# main.net
KiCad netlist of a schematic drawn in Altium Designer
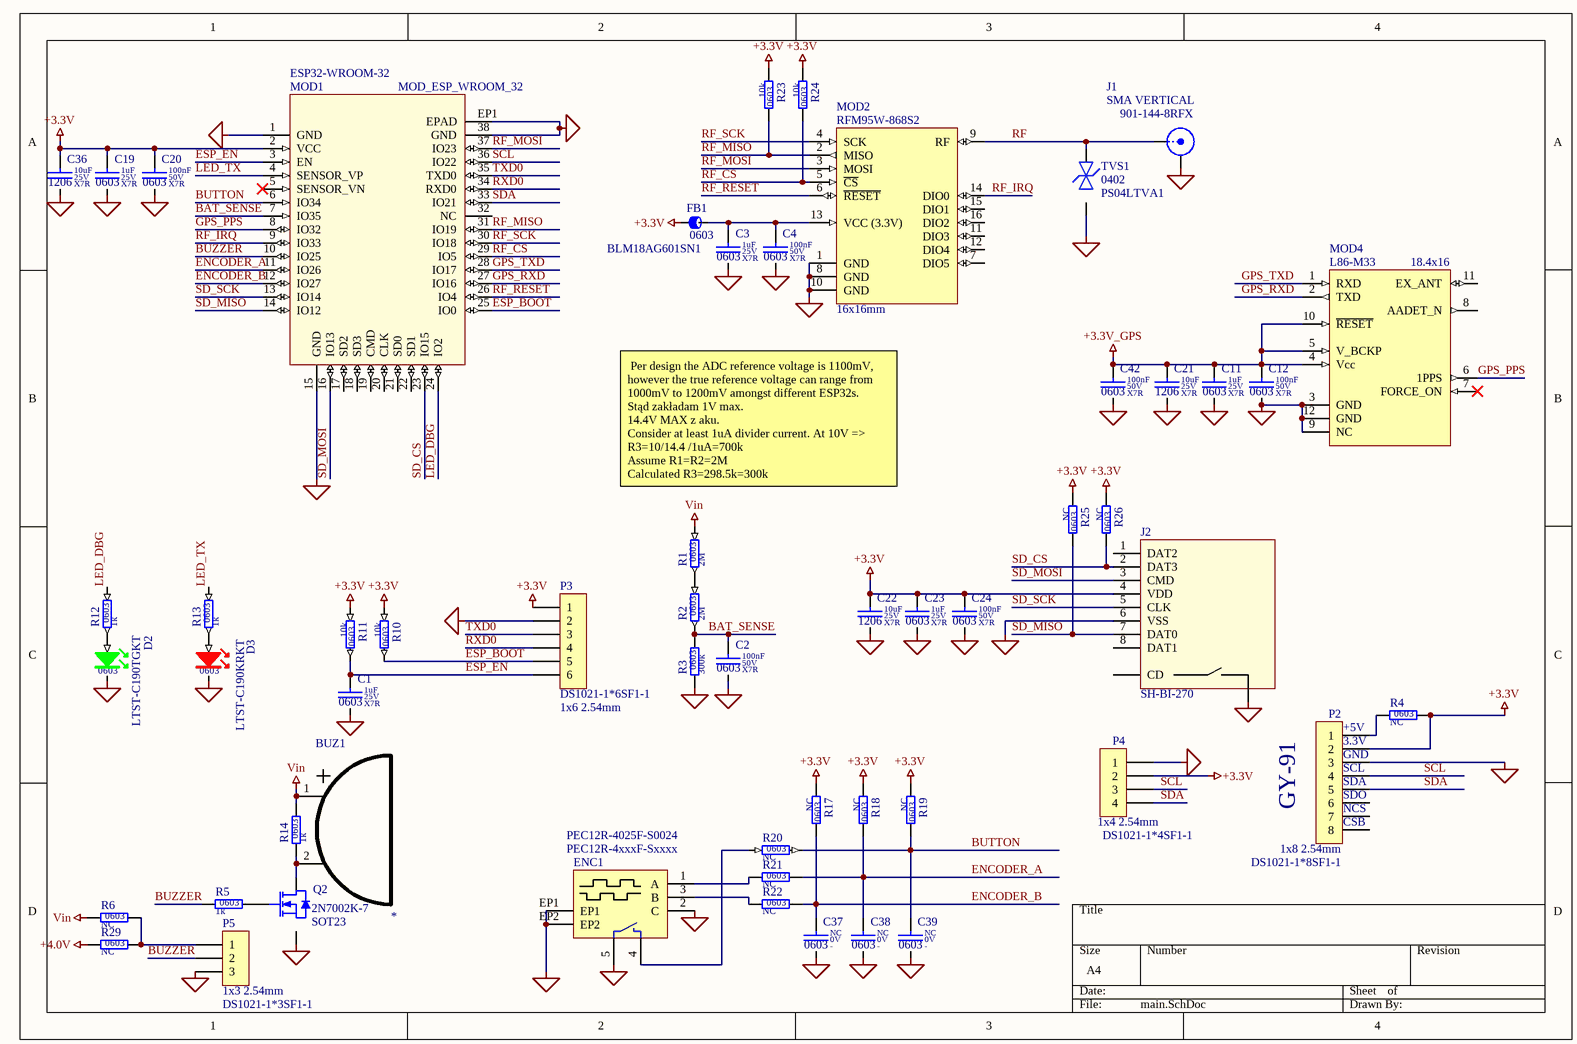
[diagram p0: main.SchDoc]

(export (version "E")
  (design (tool "Eeschema 10.0.6"))
  (components
    (comp (ref "BUZ1")
      (value "BUZ_CHINA")
      (footprint "BUZ_CHINA")
      (fields (field (name "SCH_FOOTPRINT") "*"))
      (libsource (lib "schlib") (part "BUZ_CHINA"))
    )
    (comp (ref "C1")
      (value "1uF")
      (footprint "C_0603_1608")
      (description "Capacitor")
      (fields
        (field (name "DIELECTRIC") "X7R")
        (field (name "VOLTAGE") "25V")
        (field (name "SCH_FOOTPRINT") "0603")
        (field (name "PART NUMBER") "C_1uF_25V_X7R_0603_10")
        (field (name "MANUFACTURER") "Samsung")
      )
      (libsource (lib "Library") (part "C"))
    )
    (comp (ref "C2")
      (value "100nF")
      (footprint "C_0603_1608")
      (description "Capacitor")
      (fields
        (field (name "DIELECTRIC") "X7R")
        (field (name "VOLTAGE") "50V")
        (field (name "SCH_FOOTPRINT") "0603")
        (field (name "PART NUMBER") "C_100nF_50V_X7R_0603_5")
        (field (name "MANUFACTURER") "Samsung")
      )
      (libsource (lib "Library") (part "C"))
    )
    (comp (ref "C3")
      (value "1uF")
      (footprint "C_0603_1608")
      (description "Capacitor")
      (fields
        (field (name "DIELECTRIC") "X7R")
        (field (name "VOLTAGE") "25V")
        (field (name "SCH_FOOTPRINT") "0603")
        (field (name "PART NUMBER") "C_1uF_25V_X7R_0603_10")
        (field (name "MANUFACTURER") "Samsung")
      )
      (libsource (lib "Library") (part "C"))
    )
    (comp (ref "C4")
      (value "100nF")
      (footprint "C_0603_1608")
      (description "Capacitor")
      (fields
        (field (name "DIELECTRIC") "X7R")
        (field (name "VOLTAGE") "50V")
        (field (name "SCH_FOOTPRINT") "0603")
        (field (name "PART NUMBER") "C_100nF_50V_X7R_0603_5")
        (field (name "MANUFACTURER") "Samsung")
      )
      (libsource (lib "Library") (part "C"))
    )
    (comp (ref "C11")
      (value "1uF")
      (footprint "C_0603_1608")
      (description "Capacitor")
      (fields
        (field (name "DIELECTRIC") "X7R")
        (field (name "VOLTAGE") "25V")
        (field (name "SCH_FOOTPRINT") "0603")
        (field (name "PART NUMBER") "C_1uF_25V_X7R_0603_10")
        (field (name "MANUFACTURER") "Samsung")
      )
      (libsource (lib "Library") (part "C"))
    )
    (comp (ref "C12")
      (value "100nF")
      (footprint "C_0603_1608")
      (description "Capacitor")
      (fields
        (field (name "DIELECTRIC") "X7R")
        (field (name "VOLTAGE") "50V")
        (field (name "SCH_FOOTPRINT") "0603")
        (field (name "PART NUMBER") "C_100nF_50V_X7R_0603_5")
        (field (name "MANUFACTURER") "Samsung")
      )
      (libsource (lib "Library") (part "C"))
    )
    (comp (ref "C19")
      (value "1uF")
      (footprint "C_0603_1608")
      (description "Capacitor")
      (fields
        (field (name "DIELECTRIC") "X7R")
        (field (name "VOLTAGE") "25V")
        (field (name "SCH_FOOTPRINT") "0603")
        (field (name "PART NUMBER") "C_1uF_25V_X7R_0603_10")
        (field (name "MANUFACTURER") "Samsung")
      )
      (libsource (lib "Library") (part "C"))
    )
    (comp (ref "C20")
      (value "100nF")
      (footprint "C_0603_1608")
      (description "Capacitor")
      (fields
        (field (name "DIELECTRIC") "X7R")
        (field (name "VOLTAGE") "50V")
        (field (name "SCH_FOOTPRINT") "0603")
        (field (name "PART NUMBER") "C_100nF_50V_X7R_0603_5")
        (field (name "MANUFACTURER") "Samsung")
      )
      (libsource (lib "Library") (part "C"))
    )
    (comp (ref "C21")
      (value "10uF")
      (footprint "C_1206_3216")
      (description "Capacitor")
      (fields
        (field (name "DIELECTRIC") "X7R")
        (field (name "VOLTAGE") "25V")
        (field (name "SCH_FOOTPRINT") "1206")
        (field (name "PART NUMBER") "C_10uF_25V_X7R_1206_10")
        (field (name "MANUFACTURER") "Samsung Electro-Mechanics")
      )
      (libsource (lib "Library") (part "C"))
    )
    (comp (ref "C22")
      (value "10uF")
      (footprint "C_1206_3216")
      (description "Capacitor")
      (fields
        (field (name "DIELECTRIC") "X7R")
        (field (name "VOLTAGE") "25V")
        (field (name "SCH_FOOTPRINT") "1206")
        (field (name "PART NUMBER") "C_10uF_25V_X7R_1206_10")
        (field (name "MANUFACTURER") "Samsung Electro-Mechanics")
      )
      (libsource (lib "Library") (part "C"))
    )
    (comp (ref "C23")
      (value "1uF")
      (footprint "C_0603_1608")
      (description "Capacitor")
      (fields
        (field (name "DIELECTRIC") "X7R")
        (field (name "VOLTAGE") "25V")
        (field (name "SCH_FOOTPRINT") "0603")
        (field (name "PART NUMBER") "C_1uF_25V_X7R_0603_10")
        (field (name "MANUFACTURER") "Samsung")
      )
      (libsource (lib "Library") (part "C"))
    )
    (comp (ref "C24")
      (value "100nF")
      (footprint "C_0603_1608")
      (description "Capacitor")
      (fields
        (field (name "DIELECTRIC") "X7R")
        (field (name "VOLTAGE") "50V")
        (field (name "SCH_FOOTPRINT") "0603")
        (field (name "PART NUMBER") "C_100nF_50V_X7R_0603_5")
        (field (name "MANUFACTURER") "Samsung")
      )
      (libsource (lib "Library") (part "C"))
    )
    (comp (ref "C36")
      (value "10uF")
      (footprint "C_1206_3216")
      (description "Capacitor")
      (fields
        (field (name "DIELECTRIC") "X7R")
        (field (name "VOLTAGE") "25V")
        (field (name "SCH_FOOTPRINT") "1206")
        (field (name "PART NUMBER") "C_10uF_25V_X7R_1206_10")
        (field (name "MANUFACTURER") "Samsung Electro-Mechanics")
      )
      (libsource (lib "Library") (part "C"))
    )
    (comp (ref "C37")
      (value "NC")
      (footprint "C_NC_0603_1608")
      (description "Capacitor")
      (fields
        (field (name "DIELECTRIC") "-")
        (field (name "VOLTAGE") "0V")
        (field (name "SCH_FOOTPRINT") "0603")
        (field (name "PART NUMBER") "C_GENERIC_0603")
      )
      (libsource (lib "Library") (part "C"))
    )
    (comp (ref "C38")
      (value "NC")
      (footprint "C_NC_0603_1608")
      (description "Capacitor")
      (fields
        (field (name "DIELECTRIC") "-")
        (field (name "VOLTAGE") "0V")
        (field (name "SCH_FOOTPRINT") "0603")
        (field (name "PART NUMBER") "C_GENERIC_0603")
      )
      (libsource (lib "Library") (part "C"))
    )
    (comp (ref "C39")
      (value "NC")
      (footprint "C_NC_0603_1608")
      (description "Capacitor")
      (fields
        (field (name "DIELECTRIC") "-")
        (field (name "VOLTAGE") "0V")
        (field (name "SCH_FOOTPRINT") "0603")
        (field (name "PART NUMBER") "C_GENERIC_0603")
      )
      (libsource (lib "Library") (part "C"))
    )
    (comp (ref "C42")
      (value "100nF")
      (footprint "C_0603_1608")
      (description "Capacitor")
      (fields
        (field (name "DIELECTRIC") "X7R")
        (field (name "VOLTAGE") "50V")
        (field (name "SCH_FOOTPRINT") "0603")
        (field (name "PART NUMBER") "C_100nF_50V_X7R_0603_5")
        (field (name "MANUFACTURER") "Samsung")
      )
      (libsource (lib "Library") (part "C"))
    )
    (comp (ref "D2")
      (value "LTST-C190TGKT")
      (footprint "OL_0603_1608")
      (description "LED GREEN")
      (fields
        (field (name "SCH_FOOTPRINT") "0603")
        (field (name "PART NUMBER") "OL_G_0603")
        (field (name "MANUFACTURER") "Lite-On")
      )
      (libsource (lib "Library") (part "OL_G"))
    )
    (comp (ref "D3")
      (value "LTST-C190KRKT")
      (footprint "OL_0603_1608")
      (description "LED_RED")
      (fields
        (field (name "SCH_FOOTPRINT") "0603")
        (field (name "PART NUMBER") "OL_R_0603")
        (field (name "MANUFACTURER") "Lite-On")
      )
      (libsource (lib "Library") (part "OL_R"))
    )
    (comp (ref "ENC1")
      (value "PEC12R-4025F-S0024")
      (footprint "PEC12R-4xxxF-Sxxxx")
      (fields
        (field (name "PART NUMBER") "ENC_PEC12R-4025F-S0024")
        (field (name "SCH_FOOTPRINT") "PEC12R-4xxxF-Sxxxx")
        (field (name "MANUFACTURER") "Bourns")
        (field (name "Comment") "ENCODER")
      )
      (libsource (lib "Library") (part "ENC_BUTTON"))
    )
    (comp (ref "FB1")
      (value "BLM18AG601SN1")
      (footprint "FB_0603_1608")
      (description "Ferrite Bead")
      (fields
        (field (name "PART NUMBER") "FB_BLM18AG601SN1")
        (field (name "SCH_FOOTPRINT") "0603")
        (field (name "MANUFACTURER") "Murata")
      )
      (libsource (lib "Library") (part "FB"))
    )
    (comp (ref "J1")
      (value "901-144-8RFX")
      (footprint "J_SMA_VERTICAL")
      (description "SMA connector")
      (fields
        (field (name "PART NUMBER") "J_SMA_VERTICAL")
        (field (name "SCH_FOOTPRINT") "SMA VERTICAL")
        (field (name "MANUFACTURER") "Amphenol RF")
      )
      (libsource (lib "Library") (part "J_SMA"))
    )
    (comp (ref "J2")
      (value "SH-BI-270")
      (footprint "SDCARD")
      (description "SH-BI-270 Chinese microSD socket")
      (libsource (lib "schlib") (part "sd_china"))
    )
    (comp (ref "MOD1")
      (value "ESP32-WROOM-32")
      (footprint "MOD_ESP_WROOM_32")
      (fields
        (field (name "SCH_FOOTPRINT") "MOD_ESP_WROOM_32")
        (field (name "PART NUMBER") "MOD_ESP32-WROOM-32")
        (field (name "MANUFACTURER") "ESPRESSIF")
        (field (name "Comment") "2.4 GHz Wi-Fi-and-Bluetooth combo chip")
      )
      (libsource (lib "Library") (part "MOD_ESP_WROOM_32"))
    )
    (comp (ref "MOD2")
      (value "RFM95W-868S2")
      (footprint "MOD_RFM95")
      (description "RFM95/96/97/98(W) - Low Power Long Range Transceiver Module")
      (fields
        (field (name "SCH_FOOTPRINT") "16x16mm")
        (field (name "PART NUMBER") "MOD_RFM95W-868S2")
        (field (name "MANUFACTURER") "HopeRF")
      )
      (libsource (lib "Library") (part "MOD_RFM95"))
    )
    (comp (ref "MOD4")
      (value "L86-M33")
      (footprint "MOD_L86-M33")
      (description "GPS")
      (fields
        (field (name "PART NUMBER") "MOD_L86-M33")
        (field (name "SCH_FOOTPRINT") "18.4x16")
        (field (name "MANUFACTURER") "Quectel")
      )
      (libsource (lib "Library") (part "MOD_L86-M33"))
    )
    (comp (ref "P2")
      (value "DS1021-1*8SF1-1")
      (footprint "P_HEADER_1x8_2.54")
      (description "Pin Header")
      (fields
        (field (name "SCH_FOOTPRINT") "1x8 2.54mm")
        (field (name "PART NUMBER") "P_HEADER_1x8_2.54")
        (field (name "MANUFACTURER") "Connfly")
      )
      (libsource (lib "Library") (part "P_HEADER_1x8"))
    )
    (comp (ref "P3")
      (value "DS1021-1*6SF1-1")
      (footprint "P_HEADER_1x6_2.54")
      (description "Pin Header")
      (fields
        (field (name "PART NUMBER") "P_HEADER_1x6_2.54")
        (field (name "SCH_FOOTPRINT") "1x6 2.54mm")
        (field (name "MANUFACTURER") "Connfly")
      )
      (libsource (lib "Library") (part "P_HEADER_1x6"))
    )
    (comp (ref "P4")
      (value "DS1021-1*4SF1-1")
      (footprint "P_HEADER_1x4_2.54")
      (description "Pin Header")
      (fields
        (field (name "SCH_FOOTPRINT") "1x4 2.54mm")
        (field (name "PART NUMBER") "P_HEADER_1x4_2.54")
        (field (name "MANUFACTURER") "Connfly")
      )
      (libsource (lib "Library") (part "P_HEADER_1x4"))
    )
    (comp (ref "P5")
      (value "DS1021-1*3SF1-1")
      (footprint "P_HEADER_1x3_2.54")
      (description "Pin Header")
      (fields
        (field (name "SCH_FOOTPRINT") "1x3 2.54mm")
        (field (name "PART NUMBER") "P_HEADER_1x3_2.54")
        (field (name "MANUFACTURER") "Connfly")
      )
      (libsource (lib "Library") (part "P_HEADER_1x3"))
    )
    (comp (ref "Q2")
      (value "2N7002K-7")
      (footprint "SOT23_TO236_SC59")
      (fields
        (field (name "PART NUMBER") "QN_2N7002K-7_60V_350mA")
        (field (name "SCH_FOOTPRINT") "SOT23")
        (field (name "VOLTAGE") "60V")
        (field (name "MANUFACTURER") "DIODES inc")
      )
      (libsource (lib "Library") (part "QN_GSD"))
    )
    (comp (ref "R1")
      (value "2M")
      (footprint "R_0603_1608")
      (fields
        (field (name "SCH_FOOTPRINT") "0603")
        (field (name "PART NUMBER") "R_2M_0603_1")
        (field (name "VOLTAGE") "75V")
        (field (name "POWER") "100mW")
      )
      (libsource (lib "Library") (part "R"))
    )
    (comp (ref "R2")
      (value "2M")
      (footprint "R_0603_1608")
      (fields
        (field (name "SCH_FOOTPRINT") "0603")
        (field (name "PART NUMBER") "R_2M_0603_1")
        (field (name "VOLTAGE") "75V")
        (field (name "POWER") "100mW")
      )
      (libsource (lib "Library") (part "R"))
    )
    (comp (ref "R3")
      (value "300k")
      (footprint "R_0603_1608")
      (fields
        (field (name "SCH_FOOTPRINT") "0603")
        (field (name "PART NUMBER") "R_300k_0603_5")
        (field (name "VOLTAGE") "75V")
        (field (name "POWER") "100mW")
      )
      (libsource (lib "") (part "R_1"))
    )
    (comp (ref "R4")
      (value "NC")
      (footprint "R_NC_0603_1608")
      (fields
        (field (name "SCH_FOOTPRINT") "0603")
        (field (name "PART NUMBER") "R_GENERIC_0603")
        (field (name "Comment") "Resistor")
      )
      (libsource (lib "") (part "R_1"))
    )
    (comp (ref "R5")
      (value "1k")
      (footprint "R_0603_1608")
      (fields
        (field (name "SCH_FOOTPRINT") "0603")
        (field (name "PART NUMBER") "R_1k_0603_1")
        (field (name "VOLTAGE") "75V")
        (field (name "POWER") "100mW")
      )
      (libsource (lib "") (part "R_1"))
    )
    (comp (ref "R6")
      (value "NC")
      (footprint "R_NC_0603_1608")
      (fields
        (field (name "SCH_FOOTPRINT") "0603")
        (field (name "PART NUMBER") "R_GENERIC_0603")
        (field (name "Comment") "Resistor")
      )
      (libsource (lib "") (part "R_1"))
    )
    (comp (ref "R10")
      (value "10k")
      (footprint "R_0603_1608")
      (fields
        (field (name "SCH_FOOTPRINT") "0603")
        (field (name "PART NUMBER") "R_10k_0603_1")
        (field (name "VOLTAGE") "75V")
        (field (name "POWER") "100mW")
      )
      (libsource (lib "") (part "R_2"))
    )
    (comp (ref "R11")
      (value "10k")
      (footprint "R_0603_1608")
      (fields
        (field (name "SCH_FOOTPRINT") "0603")
        (field (name "PART NUMBER") "R_10k_0603_1")
        (field (name "VOLTAGE") "75V")
        (field (name "POWER") "100mW")
      )
      (libsource (lib "") (part "R_2"))
    )
    (comp (ref "R12")
      (value "1k")
      (footprint "R_0603_1608")
      (fields
        (field (name "SCH_FOOTPRINT") "0603")
        (field (name "PART NUMBER") "R_1k_0603_1")
        (field (name "VOLTAGE") "75V")
        (field (name "POWER") "100mW")
      )
      (libsource (lib "Library") (part "R"))
    )
    (comp (ref "R13")
      (value "1k")
      (footprint "R_0603_1608")
      (fields
        (field (name "SCH_FOOTPRINT") "0603")
        (field (name "PART NUMBER") "R_1k_0603_1")
        (field (name "VOLTAGE") "75V")
        (field (name "POWER") "100mW")
      )
      (libsource (lib "Library") (part "R"))
    )
    (comp (ref "R14")
      (value "1k")
      (footprint "R_0603_1608")
      (fields
        (field (name "SCH_FOOTPRINT") "0603")
        (field (name "PART NUMBER") "R_1k_0603_1")
        (field (name "VOLTAGE") "75V")
        (field (name "POWER") "100mW")
      )
      (libsource (lib "") (part "R_1"))
    )
    (comp (ref "R17")
      (value "NC")
      (footprint "R_NC_0603_1608")
      (fields
        (field (name "SCH_FOOTPRINT") "0603")
        (field (name "PART NUMBER") "R_GENERIC_0603")
        (field (name "Comment") "Resistor")
      )
      (libsource (lib "") (part "R_1"))
    )
    (comp (ref "R18")
      (value "NC")
      (footprint "R_NC_0603_1608")
      (fields
        (field (name "SCH_FOOTPRINT") "0603")
        (field (name "PART NUMBER") "R_GENERIC_0603")
        (field (name "Comment") "Resistor")
      )
      (libsource (lib "") (part "R_1"))
    )
    (comp (ref "R19")
      (value "NC")
      (footprint "R_NC_0603_1608")
      (fields
        (field (name "SCH_FOOTPRINT") "0603")
        (field (name "PART NUMBER") "R_GENERIC_0603")
        (field (name "Comment") "Resistor")
      )
      (libsource (lib "") (part "R_1"))
    )
    (comp (ref "R20")
      (value "NC")
      (footprint "R_NC_0603_1608")
      (fields
        (field (name "SCH_FOOTPRINT") "0603")
        (field (name "PART NUMBER") "R_GENERIC_0603")
        (field (name "Comment") "Resistor")
      )
      (libsource (lib "") (part "R_2"))
    )
    (comp (ref "R21")
      (value "NC")
      (footprint "R_NC_0603_1608")
      (fields
        (field (name "SCH_FOOTPRINT") "0603")
        (field (name "PART NUMBER") "R_GENERIC_0603")
        (field (name "Comment") "Resistor")
      )
      (libsource (lib "") (part "R_1"))
    )
    (comp (ref "R22")
      (value "NC")
      (footprint "R_NC_0603_1608")
      (fields
        (field (name "SCH_FOOTPRINT") "0603")
        (field (name "PART NUMBER") "R_GENERIC_0603")
        (field (name "Comment") "Resistor")
      )
      (libsource (lib "") (part "R_1"))
    )
    (comp (ref "R23")
      (value "10k")
      (footprint "R_0603_1608")
      (fields
        (field (name "SCH_FOOTPRINT") "0603")
        (field (name "PART NUMBER") "R_10k_0603_1")
        (field (name "VOLTAGE") "75V")
        (field (name "POWER") "100mW")
      )
      (libsource (lib "") (part "R_1"))
    )
    (comp (ref "R24")
      (value "10k")
      (footprint "R_0603_1608")
      (fields
        (field (name "SCH_FOOTPRINT") "0603")
        (field (name "PART NUMBER") "R_10k_0603_1")
        (field (name "VOLTAGE") "75V")
        (field (name "POWER") "100mW")
      )
      (libsource (lib "") (part "R_1"))
    )
    (comp (ref "R25")
      (value "NC")
      (footprint "R_NC_0603_1608")
      (fields
        (field (name "SCH_FOOTPRINT") "0603")
        (field (name "PART NUMBER") "R_GENERIC_0603")
        (field (name "Comment") "Resistor")
      )
      (libsource (lib "") (part "R_1"))
    )
    (comp (ref "R26")
      (value "NC")
      (footprint "R_NC_0603_1608")
      (fields
        (field (name "SCH_FOOTPRINT") "0603")
        (field (name "PART NUMBER") "R_GENERIC_0603")
        (field (name "Comment") "Resistor")
      )
      (libsource (lib "") (part "R_1"))
    )
    (comp (ref "R29")
      (value "NC")
      (footprint "R_NC_0603_1608")
      (fields
        (field (name "SCH_FOOTPRINT") "0603")
        (field (name "PART NUMBER") "R_GENERIC_0603")
        (field (name "Comment") "Resistor")
      )
      (libsource (lib "") (part "R_1"))
    )
    (comp (ref "TVS1")
      (value "PS04LTVA1")
      (footprint "D_BI_0402_1005")
      (fields
        (field (name "SCH_FOOTPRINT") "0402")
        (field (name "PART NUMBER") "TVS_PS04LTVA1")
        (field (name "VOLTAGE") "12V")
        (field (name "MANUFACTURER") "Bussmann")
      )
      (libsource (lib "Library") (part "TVS_BI"))
    )
  )
  (nets
    (net (code "1") (name "+3.3V") (class "Default")
      (node (ref "C19") (pin "1") (pinfunction "1_1") (pintype "passive"))
      (node (ref "C20") (pin "1") (pinfunction "1_1") (pintype "passive"))
      (node (ref "C22") (pin "1") (pinfunction "1_1") (pintype "passive"))
      (node (ref "C23") (pin "1") (pinfunction "1_1") (pintype "passive"))
      (node (ref "C24") (pin "1") (pinfunction "1_1") (pintype "passive"))
      (node (ref "C36") (pin "1") (pinfunction "1_1") (pintype "passive"))
      (node (ref "FB1") (pin "1") (pintype "input"))
      (node (ref "J2") (pin "4") (pinfunction "VDD_4") (pintype "passive"))
      (node (ref "MOD1") (pin "2") (pinfunction "VCC_2") (pintype "input"))
      (node (ref "P2") (pin "2") (pinfunction "2_2") (pintype "passive"))
      (node (ref "P3") (pin "1") (pinfunction "1_1") (pintype "passive"))
      (node (ref "P4") (pin "2") (pinfunction "2_2") (pintype "passive"))
      (node (ref "R10") (pin "1") (pinfunction "1_1") (pintype "input"))
      (node (ref "R11") (pin "1") (pinfunction "1_1") (pintype "input"))
      (node (ref "R17") (pin "1") (pinfunction "1_1") (pintype "passive"))
      (node (ref "R18") (pin "1") (pinfunction "1_1") (pintype "passive"))
      (node (ref "R19") (pin "1") (pinfunction "1_1") (pintype "passive"))
      (node (ref "R23") (pin "1") (pinfunction "1_1") (pintype "passive"))
      (node (ref "R24") (pin "1") (pinfunction "1_1") (pintype "passive"))
      (node (ref "R25") (pin "1") (pinfunction "1_1") (pintype "passive"))
      (node (ref "R26") (pin "1") (pinfunction "1_1") (pintype "passive"))
      (node (ref "R4") (pin "2") (pinfunction "2_2") (pintype "passive"))
    )
    (net (code "2") (name "+3.3V_GPS") (class "Default")
      (node (ref "C11") (pin "1") (pinfunction "1_1") (pintype "passive"))
      (node (ref "C12") (pin "1") (pinfunction "1_1") (pintype "passive"))
      (node (ref "C21") (pin "1") (pinfunction "1_1") (pintype "passive"))
      (node (ref "C42") (pin "1") (pinfunction "1_1") (pintype "passive"))
      (node (ref "MOD4") (pin "10") (pinfunction "~{RESET}_10") (pintype "input"))
      (node (ref "MOD4") (pin "4") (pinfunction "Vcc_4") (pintype "input"))
      (node (ref "MOD4") (pin "5") (pinfunction "V_BCKP_5") (pintype "input"))
    )
    (net (code "3") (name "+4.0V") (class "Default")
      (node (ref "R29") (pin "1") (pinfunction "1_1") (pintype "passive"))
    )
    (net (code "4") (name "/BAT_SENSE") (class "Default")
      (node (ref "C2") (pin "1") (pinfunction "1_1") (pintype "passive"))
      (node (ref "MOD1") (pin "7") (pinfunction "IO35_7") (pintype "input"))
      (node (ref "R2") (pin "1") (pinfunction "1_1") (pintype "output"))
      (node (ref "R3") (pin "2") (pinfunction "2_2") (pintype "passive"))
    )
    (net (code "5") (name "/BUTTON") (class "Default")
      (node (ref "C39") (pin "1") (pinfunction "1_1") (pintype "passive"))
      (node (ref "MOD1") (pin "6") (pinfunction "IO34_6") (pintype "input"))
      (node (ref "R19") (pin "2") (pinfunction "2_2") (pintype "passive"))
      (node (ref "R20") (pin "2") (pinfunction "2_2") (pintype "output"))
    )
    (net (code "6") (name "/BUZZER") (class "Default")
      (node (ref "MOD1") (pin "10") (pinfunction "IO25_10") (pintype "bidirectional"))
      (node (ref "P5") (pin "2") (pinfunction "2_2") (pintype "passive"))
      (node (ref "R5") (pin "1") (pinfunction "1_1") (pintype "passive"))
    )
    (net (code "7") (name "/ENCODER_A") (class "Default")
      (node (ref "C38") (pin "1") (pinfunction "1_1") (pintype "passive"))
      (node (ref "MOD1") (pin "11") (pinfunction "IO26_11") (pintype "bidirectional"))
      (node (ref "R18") (pin "2") (pinfunction "2_2") (pintype "passive"))
      (node (ref "R21") (pin "2") (pinfunction "2_2") (pintype "passive"))
    )
    (net (code "8") (name "/ENCODER_B") (class "Default")
      (node (ref "C37") (pin "1") (pinfunction "1_1") (pintype "passive"))
      (node (ref "MOD1") (pin "12") (pinfunction "IO27_12") (pintype "bidirectional"))
      (node (ref "R17") (pin "2") (pinfunction "2_2") (pintype "passive"))
      (node (ref "R22") (pin "2") (pinfunction "2_2") (pintype "passive"))
    )
    (net (code "9") (name "/ESP_BOOT") (class "Default")
      (node (ref "MOD1") (pin "25") (pinfunction "IO0_25") (pintype "bidirectional"))
      (node (ref "P3") (pin "5") (pinfunction "5_5") (pintype "passive"))
      (node (ref "R10") (pin "2") (pinfunction "2_2") (pintype "output"))
    )
    (net (code "10") (name "/ESP_EN") (class "Default")
      (node (ref "C1") (pin "1") (pinfunction "1_1") (pintype "passive"))
      (node (ref "MOD1") (pin "3") (pinfunction "EN_3") (pintype "input"))
      (node (ref "P3") (pin "6") (pinfunction "6_6") (pintype "passive"))
      (node (ref "R11") (pin "2") (pinfunction "2_2") (pintype "output"))
    )
    (net (code "11") (name "/GPS_PPS") (class "Default")
      (node (ref "MOD1") (pin "8") (pinfunction "IO32_8") (pintype "bidirectional"))
      (node (ref "MOD4") (pin "6") (pinfunction "1PPS_6") (pintype "output"))
    )
    (net (code "12") (name "/GPS_RXD") (class "Default")
      (node (ref "MOD1") (pin "27") (pinfunction "IO16_27") (pintype "bidirectional"))
      (node (ref "MOD4") (pin "2") (pinfunction "TXD_2") (pintype "output"))
    )
    (net (code "13") (name "/GPS_TXD") (class "Default")
      (node (ref "MOD1") (pin "28") (pinfunction "IO17_28") (pintype "bidirectional"))
      (node (ref "MOD4") (pin "1") (pinfunction "RXD_1") (pintype "input"))
    )
    (net (code "14") (name "/LED_DBG") (class "Default")
      (node (ref "MOD1") (pin "24") (pinfunction "IO2_24") (pintype "bidirectional"))
      (node (ref "R12") (pin "2") (pinfunction "2_2") (pintype "input"))
    )
    (net (code "15") (name "/LED_TX") (class "Default")
      (node (ref "MOD1") (pin "4") (pinfunction "SENSOR_VP_4") (pintype "input"))
      (node (ref "R13") (pin "2") (pinfunction "2_2") (pintype "input"))
    )
    (net (code "16") (name "/RF") (class "Default")
      (node (ref "J1") (pin "1") (pinfunction "X_1") (pintype "passive"))
      (node (ref "MOD2") (pin "9") (pinfunction "RF_9") (pintype "bidirectional"))
      (node (ref "TVS1") (pin "1") (pinfunction "1_1") (pintype "passive"))
    )
    (net (code "17") (name "/RF_CS") (class "Default")
      (node (ref "MOD1") (pin "29") (pinfunction "IO5_29") (pintype "bidirectional"))
      (node (ref "MOD2") (pin "5") (pinfunction "~{CS}_5") (pintype "input"))
      (node (ref "R24") (pin "2") (pinfunction "2_2") (pintype "passive"))
    )
    (net (code "18") (name "/RF_IRQ") (class "Default")
      (node (ref "MOD1") (pin "9") (pinfunction "IO33_9") (pintype "bidirectional"))
      (node (ref "MOD2") (pin "14") (pinfunction "DIO0_14") (pintype "bidirectional"))
    )
    (net (code "19") (name "/RF_MISO") (class "Default")
      (node (ref "MOD1") (pin "31") (pinfunction "IO19_31") (pintype "bidirectional"))
      (node (ref "MOD2") (pin "2") (pinfunction "MISO_2") (pintype "output"))
      (node (ref "R23") (pin "2") (pinfunction "2_2") (pintype "passive"))
    )
    (net (code "20") (name "/RF_MOSI") (class "Default")
      (node (ref "MOD1") (pin "37") (pinfunction "IO23_37") (pintype "bidirectional"))
      (node (ref "MOD2") (pin "3") (pinfunction "MOSI_3") (pintype "input"))
    )
    (net (code "21") (name "/RF_RESET") (class "Default")
      (node (ref "MOD1") (pin "26") (pinfunction "IO4_26") (pintype "bidirectional"))
      (node (ref "MOD2") (pin "6") (pinfunction "~{RESET}_6") (pintype "bidirectional"))
    )
    (net (code "22") (name "/RF_SCK") (class "Default")
      (node (ref "MOD1") (pin "30") (pinfunction "IO18_30") (pintype "bidirectional"))
      (node (ref "MOD2") (pin "4") (pinfunction "SCK_4") (pintype "input"))
    )
    (net (code "23") (name "/RXD0") (class "Default")
      (node (ref "MOD1") (pin "34") (pinfunction "RXD0_34") (pintype "bidirectional"))
      (node (ref "P3") (pin "4") (pinfunction "4_4") (pintype "passive"))
    )
    (net (code "24") (name "/SCL") (class "Default")
      (node (ref "MOD1") (pin "36") (pinfunction "IO22_36") (pintype "bidirectional"))
      (node (ref "P2") (pin "4") (pinfunction "4_4") (pintype "passive"))
      (node (ref "P4") (pin "3") (pinfunction "3_3") (pintype "passive"))
    )
    (net (code "25") (name "/SDA") (class "Default")
      (node (ref "MOD1") (pin "33") (pinfunction "IO21_33") (pintype "bidirectional"))
      (node (ref "P2") (pin "5") (pinfunction "5_5") (pintype "passive"))
      (node (ref "P4") (pin "4") (pinfunction "4_4") (pintype "passive"))
    )
    (net (code "26") (name "/SD_CS") (class "Default")
      (node (ref "J2") (pin "2") (pinfunction "DAT3_2") (pintype "passive"))
      (node (ref "MOD1") (pin "23") (pinfunction "IO15_23") (pintype "bidirectional"))
      (node (ref "R26") (pin "2") (pinfunction "2_2") (pintype "passive"))
    )
    (net (code "27") (name "/SD_MISO") (class "Default")
      (node (ref "J2") (pin "7") (pinfunction "DAT0_7") (pintype "passive"))
      (node (ref "MOD1") (pin "14") (pinfunction "IO12_14") (pintype "bidirectional"))
      (node (ref "R25") (pin "2") (pinfunction "2_2") (pintype "passive"))
    )
    (net (code "28") (name "/SD_MOSI") (class "Default")
      (node (ref "J2") (pin "3") (pinfunction "CMD_3") (pintype "passive"))
      (node (ref "MOD1") (pin "16") (pinfunction "IO13_16") (pintype "bidirectional"))
    )
    (net (code "29") (name "/SD_SCK") (class "Default")
      (node (ref "J2") (pin "5") (pinfunction "CLK_5") (pintype "passive"))
      (node (ref "MOD1") (pin "13") (pinfunction "IO14_13") (pintype "bidirectional"))
    )
    (net (code "30") (name "/TXD0") (class "Default")
      (node (ref "MOD1") (pin "35") (pinfunction "TXD0_35") (pintype "bidirectional"))
      (node (ref "P3") (pin "3") (pinfunction "3_3") (pintype "passive"))
    )
    (net (code "31") (name "GND") (class "Default")
      (node (ref "C1") (pin "2") (pinfunction "2_2") (pintype "passive"))
      (node (ref "C11") (pin "2") (pinfunction "2_2") (pintype "passive"))
      (node (ref "C12") (pin "2") (pinfunction "2_2") (pintype "passive"))
      (node (ref "C19") (pin "2") (pinfunction "2_2") (pintype "passive"))
      (node (ref "C2") (pin "2") (pinfunction "2_2") (pintype "passive"))
      (node (ref "C20") (pin "2") (pinfunction "2_2") (pintype "passive"))
      (node (ref "C21") (pin "2") (pinfunction "2_2") (pintype "passive"))
      (node (ref "C22") (pin "2") (pinfunction "2_2") (pintype "passive"))
      (node (ref "C23") (pin "2") (pinfunction "2_2") (pintype "passive"))
      (node (ref "C24") (pin "2") (pinfunction "2_2") (pintype "passive"))
      (node (ref "C3") (pin "2") (pinfunction "2_2") (pintype "passive"))
      (node (ref "C36") (pin "2") (pinfunction "2_2") (pintype "passive"))
      (node (ref "C37") (pin "2") (pinfunction "2_2") (pintype "passive"))
      (node (ref "C38") (pin "2") (pinfunction "2_2") (pintype "passive"))
      (node (ref "C39") (pin "2") (pinfunction "2_2") (pintype "passive"))
      (node (ref "C4") (pin "2") (pinfunction "2_2") (pintype "passive"))
      (node (ref "C42") (pin "2") (pinfunction "2_2") (pintype "passive"))
      (node (ref "D2") (pin "1") (pinfunction "K_1") (pintype "output"))
      (node (ref "D3") (pin "1") (pinfunction "K_1") (pintype "output"))
      (node (ref "ENC1") (pin "2") (pinfunction "C_2") (pintype "passive"))
      (node (ref "ENC1") (pin "5") (pinfunction "SW_5") (pintype "passive"))
      (node (ref "ENC1") (pin "EP1") (pinfunction "EP1_EP1") (pintype "passive"))
      (node (ref "ENC1") (pin "EP2") (pinfunction "EP2_EP2") (pintype "passive"))
      (node (ref "J1") (pin "2") (pinfunction "GND_2") (pintype "power_in"))
      (node (ref "J2") (pin "6") (pinfunction "VSS_6") (pintype "passive"))
      (node (ref "J2") (pin "S0") (pinfunction "CD_VSS_S0") (pintype "passive"))
      (node (ref "MOD1") (pin "1") (pinfunction "GND_1") (pintype "power_in"))
      (node (ref "MOD1") (pin "15") (pinfunction "GND_15") (pintype "power_in"))
      (node (ref "MOD1") (pin "38") (pinfunction "GND_38") (pintype "power_in"))
      (node (ref "MOD1") (pin "EP1") (pinfunction "EPAD_EP1") (pintype "power_in"))
      (node (ref "MOD2") (pin "1") (pinfunction "GND_1") (pintype "power_in"))
      (node (ref "MOD2") (pin "10") (pinfunction "GND_10") (pintype "power_in"))
      (node (ref "MOD2") (pin "8") (pinfunction "GND_8") (pintype "power_in"))
      (node (ref "MOD4") (pin "12") (pinfunction "GND_12") (pintype "power_in"))
      (node (ref "MOD4") (pin "3") (pinfunction "GND_3") (pintype "power_in"))
      (node (ref "MOD4") (pin "9") (pinfunction "NC_9") (pintype "passive"))
      (node (ref "P2") (pin "3") (pinfunction "3_3") (pintype "passive"))
      (node (ref "P3") (pin "2") (pinfunction "2_2") (pintype "passive"))
      (node (ref "P4") (pin "1") (pinfunction "1_1") (pintype "passive"))
      (node (ref "P5") (pin "3") (pinfunction "3_3") (pintype "passive"))
      (node (ref "Q2") (pin "2") (pinfunction "S_2") (pintype "passive"))
      (node (ref "R3") (pin "1") (pinfunction "1_1") (pintype "passive"))
      (node (ref "TVS1") (pin "2") (pinfunction "2_2") (pintype "passive"))
    )
    (net (code "32") (name "Net-(D2-A)") (class "Default")
      (node (ref "D2") (pin "2") (pinfunction "A_2") (pintype "input"))
      (node (ref "R12") (pin "1") (pinfunction "1_1") (pintype "output"))
    )
    (net (code "33") (name "Net-(D3-A)") (class "Default")
      (node (ref "D3") (pin "2") (pinfunction "A_2") (pintype "input"))
      (node (ref "R13") (pin "1") (pinfunction "1_1") (pintype "output"))
    )
    (net (code "34") (name "Net-(ENC1-A)") (class "Default")
      (node (ref "ENC1") (pin "1") (pinfunction "A_1") (pintype "passive"))
      (node (ref "R21") (pin "1") (pinfunction "1_1") (pintype "passive"))
    )
    (net (code "35") (name "Net-(ENC1-B)") (class "Default")
      (node (ref "ENC1") (pin "3") (pinfunction "B_3") (pintype "passive"))
      (node (ref "R22") (pin "1") (pinfunction "1_1") (pintype "passive"))
    )
    (net (code "36") (name "Net-(ENC1-SW-Pad4)") (class "Default")
      (node (ref "ENC1") (pin "4") (pinfunction "SW_4") (pintype "passive"))
      (node (ref "R20") (pin "1") (pinfunction "1_1") (pintype "input"))
    )
    (net (code "37") (name "Net-(MOD2-VCC_(3.3V))") (class "Default")
      (node (ref "C3") (pin "1") (pinfunction "1_1") (pintype "passive"))
      (node (ref "C4") (pin "1") (pinfunction "1_1") (pintype "passive"))
      (node (ref "FB1") (pin "2") (pintype "output"))
      (node (ref "MOD2") (pin "13") (pinfunction "VCC_(3.3V)_13") (pintype "input"))
    )
    (net (code "38") (name "Net-(P2-Pad1)") (class "Default")
      (node (ref "P2") (pin "1") (pinfunction "1_1") (pintype "passive"))
      (node (ref "R4") (pin "1") (pinfunction "1_1") (pintype "passive"))
    )
    (net (code "39") (name "Net-(P5-Pad1)") (class "Default")
      (node (ref "P5") (pin "1") (pinfunction "1_1") (pintype "passive"))
      (node (ref "R29") (pin "2") (pinfunction "2_2") (pintype "passive"))
      (node (ref "R6") (pin "2") (pinfunction "2_2") (pintype "passive"))
    )
    (net (code "40") (name "Net-(Q2-D)") (class "Default")
      (node (ref "BUZ1") (pin "2") (pinfunction "2_2") (pintype "passive"))
      (node (ref "Q2") (pin "3") (pinfunction "D_3") (pintype "passive"))
      (node (ref "R14") (pin "1") (pinfunction "1_1") (pintype "passive"))
    )
    (net (code "41") (name "Net-(Q2-G)") (class "Default")
      (node (ref "Q2") (pin "1") (pinfunction "G_1") (pintype "passive"))
      (node (ref "R5") (pin "2") (pinfunction "2_2") (pintype "passive"))
    )
    (net (code "42") (name "Net-(R1-Pad1)") (class "Default")
      (node (ref "R1") (pin "1") (pinfunction "1_1") (pintype "output"))
      (node (ref "R2") (pin "2") (pinfunction "2_2") (pintype "input"))
    )
    (net (code "43") (name "Vin") (class "Default")
      (node (ref "BUZ1") (pin "1") (pinfunction "1_1") (pintype "passive"))
      (node (ref "R1") (pin "2") (pinfunction "2_2") (pintype "input"))
      (node (ref "R14") (pin "2") (pinfunction "2_2") (pintype "passive"))
      (node (ref "R6") (pin "1") (pinfunction "1_1") (pintype "passive"))
    )
    (net (code "44") (name "unconnected-(J2-DAT1-Pad8)") (class "Default")
      (node (ref "J2") (pin "8") (pinfunction "DAT1_8") (pintype "passive"))
    )
    (net (code "45") (name "unconnected-(J2-DAT2-Pad1)") (class "Default")
      (node (ref "J2") (pin "1") (pinfunction "DAT2_1") (pintype "passive"))
    )
    (net (code "46") (name "unconnected-(J2-PadCD)") (class "Default")
      (node (ref "J2") (pin "CD") (pinfunction "CD_CD") (pintype "passive"))
    )
    (net (code "47") (name "unconnected-(MOD1-CLK-Pad20)") (class "Default")
      (node (ref "MOD1") (pin "20") (pinfunction "CLK_20") (pintype "bidirectional"))
    )
    (net (code "48") (name "unconnected-(MOD1-CMD-Pad19)") (class "Default")
      (node (ref "MOD1") (pin "19") (pinfunction "CMD_19") (pintype "bidirectional"))
    )
    (net (code "49") (name "unconnected-(MOD1-NC-Pad32)") (class "Default")
      (node (ref "MOD1") (pin "32") (pinfunction "NC_32") (pintype "passive"))
    )
    (net (code "50") (name "unconnected-(MOD1-SD0-Pad21)") (class "Default")
      (node (ref "MOD1") (pin "21") (pinfunction "SD0_21") (pintype "bidirectional"))
    )
    (net (code "51") (name "unconnected-(MOD1-SD1-Pad22)") (class "Default")
      (node (ref "MOD1") (pin "22") (pinfunction "SD1_22") (pintype "bidirectional"))
    )
    (net (code "52") (name "unconnected-(MOD1-SD2-Pad17)") (class "Default")
      (node (ref "MOD1") (pin "17") (pinfunction "SD2_17") (pintype "bidirectional"))
    )
    (net (code "53") (name "unconnected-(MOD1-SD3-Pad18)") (class "Default")
      (node (ref "MOD1") (pin "18") (pinfunction "SD3_18") (pintype "bidirectional"))
    )
    (net (code "54") (name "unconnected-(MOD1-SENSOR_VN-Pad5)") (class "Default")
      (node (ref "MOD1") (pin "5") (pinfunction "SENSOR_VN_5") (pintype "input+no_connect"))
    )
    (net (code "55") (name "unconnected-(MOD2-DIO1-Pad15)") (class "Default")
      (node (ref "MOD2") (pin "15") (pinfunction "DIO1_15") (pintype "bidirectional"))
    )
    (net (code "56") (name "unconnected-(MOD2-DIO2-Pad16)") (class "Default")
      (node (ref "MOD2") (pin "16") (pinfunction "DIO2_16") (pintype "bidirectional"))
    )
    (net (code "57") (name "unconnected-(MOD2-DIO3-Pad11)") (class "Default")
      (node (ref "MOD2") (pin "11") (pinfunction "DIO3_11") (pintype "bidirectional"))
    )
    (net (code "58") (name "unconnected-(MOD2-DIO4-Pad12)") (class "Default")
      (node (ref "MOD2") (pin "12") (pinfunction "DIO4_12") (pintype "bidirectional"))
    )
    (net (code "59") (name "unconnected-(MOD2-DIO5-Pad7)") (class "Default")
      (node (ref "MOD2") (pin "7") (pinfunction "DIO5_7") (pintype "bidirectional"))
    )
    (net (code "60") (name "unconnected-(MOD4-AADET_N-Pad8)") (class "Default")
      (node (ref "MOD4") (pin "8") (pinfunction "AADET_N_8") (pintype "output"))
    )
    (net (code "61") (name "unconnected-(MOD4-EX_ANT-Pad11)") (class "Default")
      (node (ref "MOD4") (pin "11") (pinfunction "EX_ANT_11") (pintype "bidirectional"))
    )
    (net (code "62") (name "unconnected-(MOD4-FORCE_ON-Pad7)") (class "Default")
      (node (ref "MOD4") (pin "7") (pinfunction "FORCE_ON_7") (pintype "input+no_connect"))
    )
    (net (code "63") (name "unconnected-(P2-Pad6)") (class "Default")
      (node (ref "P2") (pin "6") (pinfunction "6_6") (pintype "passive"))
    )
    (net (code "64") (name "unconnected-(P2-Pad7)") (class "Default")
      (node (ref "P2") (pin "7") (pinfunction "7_7") (pintype "passive"))
    )
    (net (code "65") (name "unconnected-(P2-Pad8)") (class "Default")
      (node (ref "P2") (pin "8") (pinfunction "8_8") (pintype "passive"))
    )
  )
)
